# SMARTCONTROL2.net
KiCad netlist of a schematic drawn in EAGLE
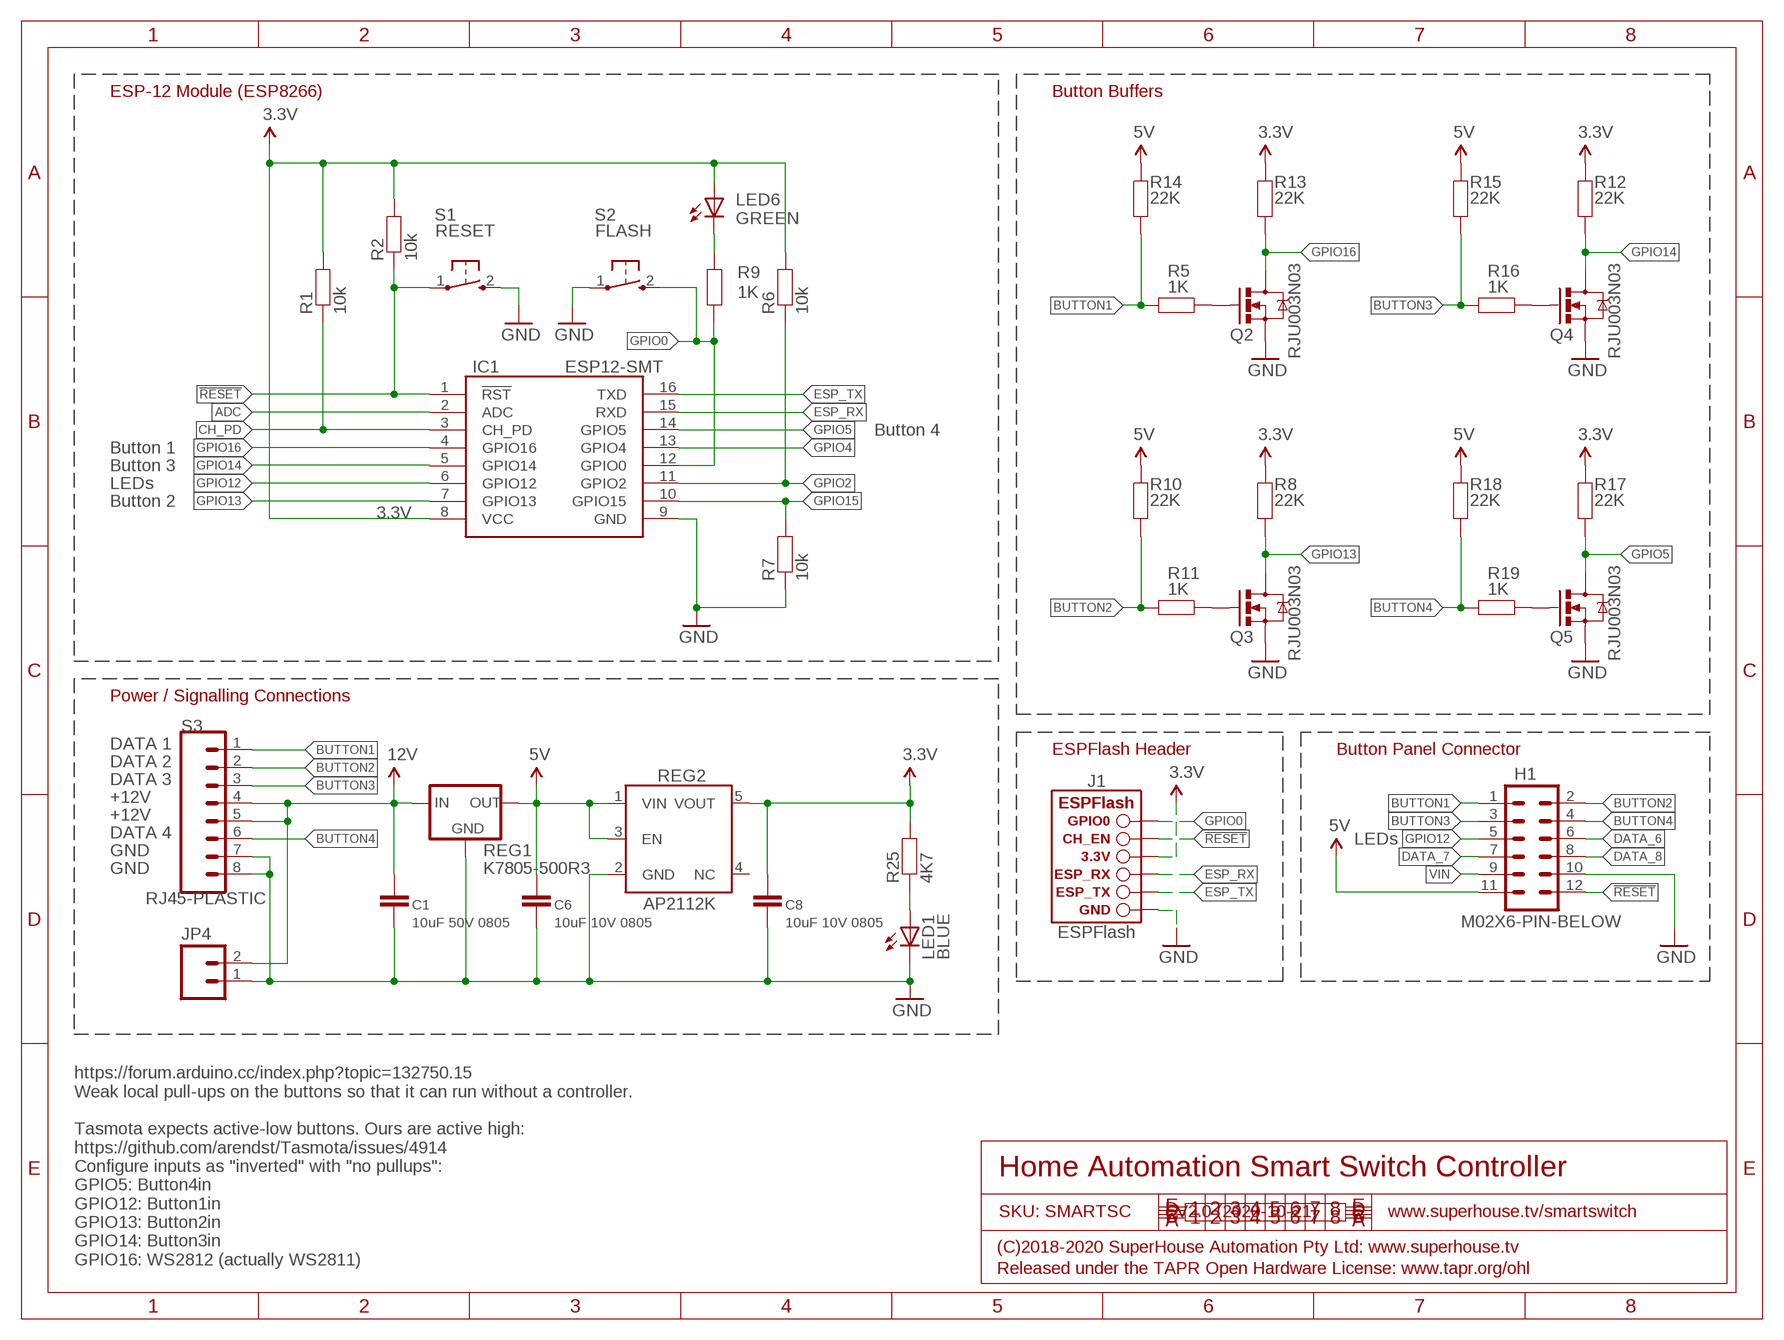
[diagram p0: schematic, sheet 1]

(export (version "E")
  (design (tool "Eeschema 10.0.6"))
  (components
    (comp (ref "C1")
      (value "10uF 50V 0805")
      (footprint "eagle-import:C0805")
      (libsource (lib "eagle-import") (part "CAP0805"))
    )
    (comp (ref "C6")
      (value "10uF 10V 0805")
      (footprint "eagle-import:C0805")
      (libsource (lib "eagle-import") (part "CAP0805"))
    )
    (comp (ref "C8")
      (value "10uF 10V 0805")
      (footprint "eagle-import:C0805")
      (libsource (lib "eagle-import") (part "CAP0805"))
    )
    (comp (ref "H1")
      (value "M02X6-PIN-BELOW")
      (footprint "eagle-import:2X06-P-BELOW")
      (libsource (lib "eagle-import") (part "M02X6-PIN-BELOW"))
    )
    (comp (ref "IC1")
      (value "ESP12-SMT")
      (footprint "eagle-import:ESP12")
      (libsource (lib "eagle-import") (part "ESP12-SMT"))
    )
    (comp (ref "J1")
      (value "ESPFLASH-1X6-2.54-SOCKET")
      (footprint "eagle-import:1X6-2.54-SOCKET")
      (libsource (lib "eagle-import") (part "ESPFLASH-1X6-2.54-SOCKET"))
    )
    (comp (ref "JP4")
      (value "M02-SCREW-5MM")
      (footprint "eagle-import:SCREWTERMINAL-5MM-2")
      (libsource (lib "eagle-import") (part "M02-SCREW-5MM"))
    )
    (comp (ref "LED1")
      (value "BLUE")
      (footprint "eagle-import:LED-0603")
      (libsource (lib "eagle-import") (part "LED0603"))
    )
    (comp (ref "LED6")
      (value "GREEN")
      (footprint "eagle-import:LED-0603")
      (libsource (lib "eagle-import") (part "LED0603"))
    )
    (comp (ref "Q2")
      (value "RJU003N03")
      (footprint "eagle-import:SOT32-3")
      (libsource (lib "eagle-import") (part "MOSFET-NCHANNEL-323"))
    )
    (comp (ref "Q3")
      (value "RJU003N03")
      (footprint "eagle-import:SOT32-3")
      (libsource (lib "eagle-import") (part "MOSFET-NCHANNEL-323"))
    )
    (comp (ref "Q4")
      (value "RJU003N03")
      (footprint "eagle-import:SOT32-3")
      (libsource (lib "eagle-import") (part "MOSFET-NCHANNEL-323"))
    )
    (comp (ref "Q5")
      (value "RJU003N03")
      (footprint "eagle-import:SOT32-3")
      (libsource (lib "eagle-import") (part "MOSFET-NCHANNEL-323"))
    )
    (comp (ref "R1")
      (value "10k")
      (footprint "eagle-import:R0603")
      (libsource (lib "eagle-import") (part "RESISTOR0603"))
    )
    (comp (ref "R2")
      (value "10k")
      (footprint "eagle-import:R0603")
      (libsource (lib "eagle-import") (part "RESISTOR0603"))
    )
    (comp (ref "R5")
      (value "1K")
      (footprint "eagle-import:R0603")
      (libsource (lib "eagle-import") (part "RESISTOR0603"))
    )
    (comp (ref "R6")
      (value "10k")
      (footprint "eagle-import:R0603")
      (libsource (lib "eagle-import") (part "RESISTOR0603"))
    )
    (comp (ref "R7")
      (value "10k")
      (footprint "eagle-import:R0603")
      (libsource (lib "eagle-import") (part "RESISTOR0603"))
    )
    (comp (ref "R8")
      (value "22K")
      (footprint "eagle-import:R0603")
      (libsource (lib "eagle-import") (part "RESISTOR0603"))
    )
    (comp (ref "R9")
      (value "1K")
      (footprint "eagle-import:R0603")
      (libsource (lib "eagle-import") (part "RESISTOR0603"))
    )
    (comp (ref "R10")
      (value "22K")
      (footprint "eagle-import:R0603")
      (libsource (lib "eagle-import") (part "RESISTOR0603"))
    )
    (comp (ref "R11")
      (value "1K")
      (footprint "eagle-import:R0603")
      (libsource (lib "eagle-import") (part "RESISTOR0603"))
    )
    (comp (ref "R12")
      (value "22K")
      (footprint "eagle-import:R0603")
      (libsource (lib "eagle-import") (part "RESISTOR0603"))
    )
    (comp (ref "R13")
      (value "22K")
      (footprint "eagle-import:R0603")
      (libsource (lib "eagle-import") (part "RESISTOR0603"))
    )
    (comp (ref "R14")
      (value "22K")
      (footprint "eagle-import:R0603")
      (libsource (lib "eagle-import") (part "RESISTOR0603"))
    )
    (comp (ref "R15")
      (value "22K")
      (footprint "eagle-import:R0603")
      (libsource (lib "eagle-import") (part "RESISTOR0603"))
    )
    (comp (ref "R16")
      (value "1K")
      (footprint "eagle-import:R0603")
      (libsource (lib "eagle-import") (part "RESISTOR0603"))
    )
    (comp (ref "R17")
      (value "22K")
      (footprint "eagle-import:R0603")
      (libsource (lib "eagle-import") (part "RESISTOR0603"))
    )
    (comp (ref "R18")
      (value "22K")
      (footprint "eagle-import:R0603")
      (libsource (lib "eagle-import") (part "RESISTOR0603"))
    )
    (comp (ref "R19")
      (value "1K")
      (footprint "eagle-import:R0603")
      (libsource (lib "eagle-import") (part "RESISTOR0603"))
    )
    (comp (ref "R25")
      (value "4K7")
      (footprint "eagle-import:R0603")
      (libsource (lib "eagle-import") (part "RESISTOR0603"))
    )
    (comp (ref "REG1")
      (value "K7805-500R3")
      (footprint "eagle-import:K78XX-500R3")
      (libsource (lib "eagle-import") (part "78XX-K78XX-VERTICAL"))
    )
    (comp (ref "REG2")
      (value "AP2112KSOT25")
      (footprint "eagle-import:SOT23-5")
      (libsource (lib "eagle-import") (part "AP2112KSOT25"))
    )
    (comp (ref "S1")
      (value "RESET")
      (footprint "eagle-import:TACTILE_SMT_3X4X2")
      (libsource (lib "eagle-import") (part "TAC_SWITCH_2PINSMT"))
    )
    (comp (ref "S2")
      (value "FLASH")
      (footprint "eagle-import:TACTILE_SMT_3X4X2")
      (libsource (lib "eagle-import") (part "TAC_SWITCH_2PINSMT"))
    )
    (comp (ref "S3")
      (value "RJ45-PLASTIC")
      (footprint "eagle-import:RJ45")
      (libsource (lib "eagle-import") (part "RJ45-PLASTIC"))
    )
  )
  (nets
    (net (code "1") (name "/~{RESET}") (class "Default")
      (node (ref "H1") (pin "12") (pinfunction "12_12") (pintype "passive"))
      (node (ref "IC1") (pin "1") (pinfunction "~{RST}_1") (pintype "bidirectional"))
      (node (ref "J1") (pin "5") (pinfunction "CH_EN_5") (pintype "passive"))
      (node (ref "R2") (pin "1") (pinfunction "1_1") (pintype "passive"))
      (node (ref "S1") (pin "1") (pinfunction "P_1") (pintype "passive"))
    )
    (net (code "2") (name "3.3V") (class "Default")
      (node (ref "C8") (pin "1") (pinfunction "1_1") (pintype "passive"))
      (node (ref "IC1") (pin "8") (pinfunction "VCC_8") (pintype "power_in"))
      (node (ref "J1") (pin "4") (pinfunction "3.3V_4") (pintype "passive"))
      (node (ref "LED6") (pin "A") (pinfunction "A_A") (pintype "passive"))
      (node (ref "R1") (pin "2") (pinfunction "2_2") (pintype "passive"))
      (node (ref "R12") (pin "2") (pinfunction "2_2") (pintype "passive"))
      (node (ref "R13") (pin "2") (pinfunction "2_2") (pintype "passive"))
      (node (ref "R17") (pin "2") (pinfunction "2_2") (pintype "passive"))
      (node (ref "R2") (pin "2") (pinfunction "2_2") (pintype "passive"))
      (node (ref "R25") (pin "2") (pinfunction "2_2") (pintype "passive"))
      (node (ref "R6") (pin "2") (pinfunction "2_2") (pintype "passive"))
      (node (ref "R8") (pin "2") (pinfunction "2_2") (pintype "passive"))
      (node (ref "REG2") (pin "5") (pinfunction "VOUT_5") (pintype "bidirectional"))
    )
    (net (code "3") (name "5V") (class "Default")
      (node (ref "C6") (pin "1") (pinfunction "1_1") (pintype "passive"))
      (node (ref "H1") (pin "11") (pinfunction "11_11") (pintype "passive"))
      (node (ref "R10") (pin "2") (pinfunction "2_2") (pintype "passive"))
      (node (ref "R14") (pin "2") (pinfunction "2_2") (pintype "passive"))
      (node (ref "R15") (pin "2") (pinfunction "2_2") (pintype "passive"))
      (node (ref "R18") (pin "2") (pinfunction "2_2") (pintype "passive"))
      (node (ref "REG1") (pin "3") (pinfunction "OUT_3") (pintype "output"))
      (node (ref "REG2") (pin "1") (pinfunction "VIN_1") (pintype "bidirectional"))
      (node (ref "REG2") (pin "3") (pinfunction "EN_3") (pintype "bidirectional"))
    )
    (net (code "4") (name "12V") (class "Default")
      (node (ref "C1") (pin "1") (pinfunction "1_1") (pintype "passive"))
      (node (ref "JP4") (pin "2") (pinfunction "2_2") (pintype "passive"))
      (node (ref "REG1") (pin "1") (pinfunction "IN_1") (pintype "input"))
      (node (ref "S3") (pin "4") (pinfunction "4_4") (pintype "passive"))
      (node (ref "S3") (pin "5") (pinfunction "5_5") (pintype "passive"))
    )
    (net (code "5") (name "ADC") (class "Default")
      (node (ref "IC1") (pin "2") (pinfunction "ADC_2") (pintype "input"))
    )
    (net (code "6") (name "BUTTON1") (class "Default")
      (node (ref "H1") (pin "1") (pinfunction "1_1") (pintype "passive"))
      (node (ref "R14") (pin "1") (pinfunction "1_1") (pintype "passive"))
      (node (ref "R5") (pin "2") (pinfunction "2_2") (pintype "passive"))
      (node (ref "S3") (pin "1") (pinfunction "1_1") (pintype "passive"))
    )
    (net (code "7") (name "BUTTON2") (class "Default")
      (node (ref "H1") (pin "2") (pinfunction "2_2") (pintype "passive"))
      (node (ref "R10") (pin "1") (pinfunction "1_1") (pintype "passive"))
      (node (ref "R11") (pin "2") (pinfunction "2_2") (pintype "passive"))
      (node (ref "S3") (pin "2") (pinfunction "2_2") (pintype "passive"))
    )
    (net (code "8") (name "BUTTON3") (class "Default")
      (node (ref "H1") (pin "3") (pinfunction "3_3") (pintype "passive"))
      (node (ref "R15") (pin "1") (pinfunction "1_1") (pintype "passive"))
      (node (ref "R16") (pin "2") (pinfunction "2_2") (pintype "passive"))
      (node (ref "S3") (pin "3") (pinfunction "3_3") (pintype "passive"))
    )
    (net (code "9") (name "BUTTON4") (class "Default")
      (node (ref "H1") (pin "4") (pinfunction "4_4") (pintype "passive"))
      (node (ref "R18") (pin "1") (pinfunction "1_1") (pintype "passive"))
      (node (ref "R19") (pin "2") (pinfunction "2_2") (pintype "passive"))
      (node (ref "S3") (pin "6") (pinfunction "6_6") (pintype "passive"))
    )
    (net (code "10") (name "CH_PD") (class "Default")
      (node (ref "IC1") (pin "3") (pinfunction "CH_PD_3") (pintype "input"))
      (node (ref "R1") (pin "1") (pinfunction "1_1") (pintype "passive"))
    )
    (net (code "11") (name "DATA_6") (class "Default")
      (node (ref "H1") (pin "6") (pinfunction "6_6") (pintype "passive"))
    )
    (net (code "12") (name "DATA_7") (class "Default")
      (node (ref "H1") (pin "7") (pinfunction "7_7") (pintype "passive"))
    )
    (net (code "13") (name "DATA_8") (class "Default")
      (node (ref "H1") (pin "8") (pinfunction "8_8") (pintype "passive"))
    )
    (net (code "14") (name "ESP_RX") (class "Default")
      (node (ref "IC1") (pin "15") (pinfunction "RXD_15") (pintype "input"))
      (node (ref "J1") (pin "3") (pinfunction "ESP_RX_3") (pintype "passive"))
    )
    (net (code "15") (name "ESP_TX") (class "Default")
      (node (ref "IC1") (pin "16") (pinfunction "TXD_16") (pintype "output"))
      (node (ref "J1") (pin "2") (pinfunction "ESP_TX_2") (pintype "passive"))
    )
    (net (code "16") (name "GND") (class "Default")
      (node (ref "C1") (pin "2") (pinfunction "2_2") (pintype "passive"))
      (node (ref "C6") (pin "2") (pinfunction "2_2") (pintype "passive"))
      (node (ref "C8") (pin "2") (pinfunction "2_2") (pintype "passive"))
      (node (ref "H1") (pin "10") (pinfunction "10_10") (pintype "passive"))
      (node (ref "IC1") (pin "9") (pinfunction "GND_9") (pintype "power_in"))
      (node (ref "J1") (pin "1") (pinfunction "GND_1") (pintype "passive"))
      (node (ref "JP4") (pin "1") (pinfunction "1_1") (pintype "passive"))
      (node (ref "LED1") (pin "C") (pinfunction "C_C") (pintype "passive"))
      (node (ref "Q2") (pin "2") (pinfunction "S_2") (pintype "passive"))
      (node (ref "Q3") (pin "2") (pinfunction "S_2") (pintype "passive"))
      (node (ref "Q4") (pin "2") (pinfunction "S_2") (pintype "passive"))
      (node (ref "Q5") (pin "2") (pinfunction "S_2") (pintype "passive"))
      (node (ref "R7") (pin "1") (pinfunction "1_1") (pintype "passive"))
      (node (ref "REG1") (pin "2") (pinfunction "GND_2") (pintype "input"))
      (node (ref "REG2") (pin "2") (pinfunction "GND_2") (pintype "bidirectional"))
      (node (ref "S1") (pin "2") (pinfunction "S_2") (pintype "passive"))
      (node (ref "S2") (pin "1") (pinfunction "P_1") (pintype "passive"))
      (node (ref "S3") (pin "7") (pinfunction "7_7") (pintype "passive"))
      (node (ref "S3") (pin "8") (pinfunction "8_8") (pintype "passive"))
    )
    (net (code "17") (name "GPIO0") (class "Default")
      (node (ref "IC1") (pin "12") (pinfunction "GPIO0_12") (pintype "bidirectional"))
      (node (ref "J1") (pin "6") (pinfunction "GPIO0_6") (pintype "passive"))
      (node (ref "R9") (pin "2") (pinfunction "2_2") (pintype "passive"))
      (node (ref "S2") (pin "2") (pinfunction "S_2") (pintype "passive"))
    )
    (net (code "18") (name "GPIO2") (class "Default")
      (node (ref "IC1") (pin "11") (pinfunction "GPIO2_11") (pintype "bidirectional"))
      (node (ref "R6") (pin "1") (pinfunction "1_1") (pintype "passive"))
    )
    (net (code "19") (name "GPIO4") (class "Default")
      (node (ref "IC1") (pin "13") (pinfunction "GPIO4_13") (pintype "bidirectional"))
    )
    (net (code "20") (name "GPIO5") (class "Default")
      (node (ref "IC1") (pin "14") (pinfunction "GPIO5_14") (pintype "bidirectional"))
      (node (ref "Q5") (pin "3") (pinfunction "D_3") (pintype "passive"))
      (node (ref "R17") (pin "1") (pinfunction "1_1") (pintype "passive"))
    )
    (net (code "21") (name "GPIO12") (class "Default")
      (node (ref "H1") (pin "5") (pinfunction "5_5") (pintype "passive"))
      (node (ref "IC1") (pin "6") (pinfunction "GPIO12_6") (pintype "bidirectional"))
    )
    (net (code "22") (name "GPIO13") (class "Default")
      (node (ref "IC1") (pin "7") (pinfunction "GPIO13_7") (pintype "bidirectional"))
      (node (ref "Q3") (pin "3") (pinfunction "D_3") (pintype "passive"))
      (node (ref "R8") (pin "1") (pinfunction "1_1") (pintype "passive"))
    )
    (net (code "23") (name "GPIO14") (class "Default")
      (node (ref "IC1") (pin "5") (pinfunction "GPIO14_5") (pintype "bidirectional"))
      (node (ref "Q4") (pin "3") (pinfunction "D_3") (pintype "passive"))
      (node (ref "R12") (pin "1") (pinfunction "1_1") (pintype "passive"))
    )
    (net (code "24") (name "GPIO15") (class "Default")
      (node (ref "IC1") (pin "10") (pinfunction "GPIO15_10") (pintype "bidirectional"))
      (node (ref "R7") (pin "2") (pinfunction "2_2") (pintype "passive"))
    )
    (net (code "25") (name "GPIO16") (class "Default")
      (node (ref "IC1") (pin "4") (pinfunction "GPIO16_4") (pintype "bidirectional"))
      (node (ref "Q2") (pin "3") (pinfunction "D_3") (pintype "passive"))
      (node (ref "R13") (pin "1") (pinfunction "1_1") (pintype "passive"))
    )
    (net (code "26") (name "Net-(LED1-PadA)") (class "Default")
      (node (ref "LED1") (pin "A") (pinfunction "A_A") (pintype "passive"))
      (node (ref "R25") (pin "1") (pinfunction "1_1") (pintype "passive"))
    )
    (net (code "27") (name "Net-(LED6-PadC)") (class "Default")
      (node (ref "LED6") (pin "C") (pinfunction "C_C") (pintype "passive"))
      (node (ref "R9") (pin "1") (pinfunction "1_1") (pintype "passive"))
    )
    (net (code "28") (name "Net-(Q2-G)") (class "Default")
      (node (ref "Q2") (pin "1") (pinfunction "G_1") (pintype "passive"))
      (node (ref "R5") (pin "1") (pinfunction "1_1") (pintype "passive"))
    )
    (net (code "29") (name "Net-(Q3-G)") (class "Default")
      (node (ref "Q3") (pin "1") (pinfunction "G_1") (pintype "passive"))
      (node (ref "R11") (pin "1") (pinfunction "1_1") (pintype "passive"))
    )
    (net (code "30") (name "Net-(Q4-G)") (class "Default")
      (node (ref "Q4") (pin "1") (pinfunction "G_1") (pintype "passive"))
      (node (ref "R16") (pin "1") (pinfunction "1_1") (pintype "passive"))
    )
    (net (code "31") (name "Net-(Q5-G)") (class "Default")
      (node (ref "Q5") (pin "1") (pinfunction "G_1") (pintype "passive"))
      (node (ref "R19") (pin "1") (pinfunction "1_1") (pintype "passive"))
    )
    (net (code "32") (name "VIN") (class "Default")
      (node (ref "H1") (pin "9") (pinfunction "9_9") (pintype "passive"))
    )
    (net (code "33") (name "unconnected-(REG2-NC-Pad4)") (class "Default")
      (node (ref "REG2") (pin "4") (pinfunction "NC_4") (pintype "bidirectional"))
    )
  )
)
